# simple-loop-active2.net
KiCad netlist of a schematic drawn in EAGLE
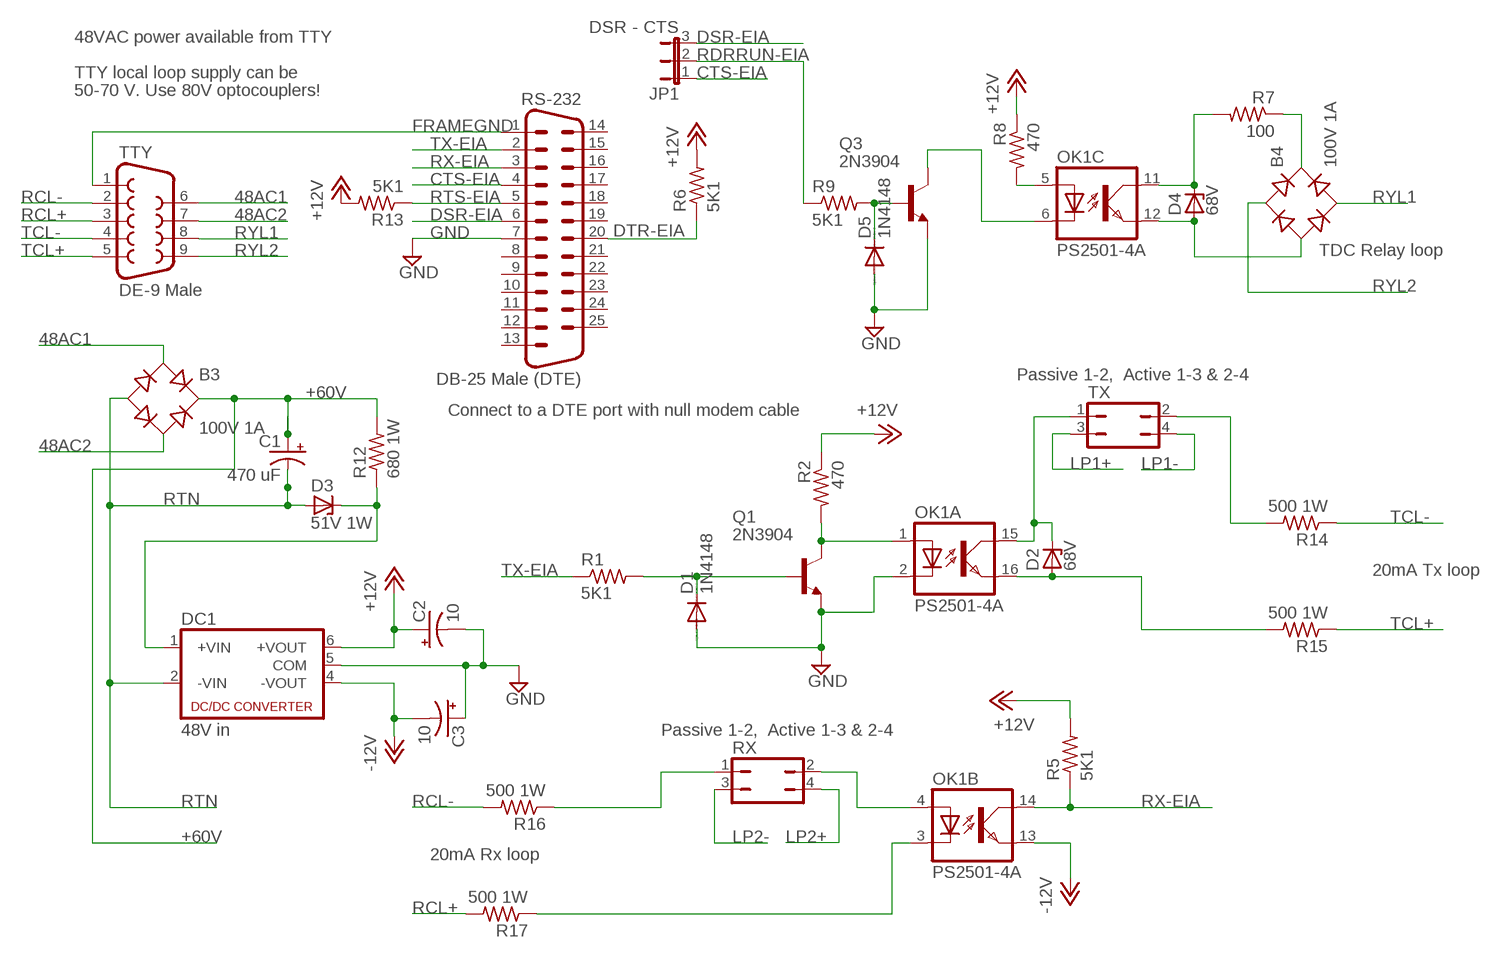
[diagram p0: schematic, sheet 1]
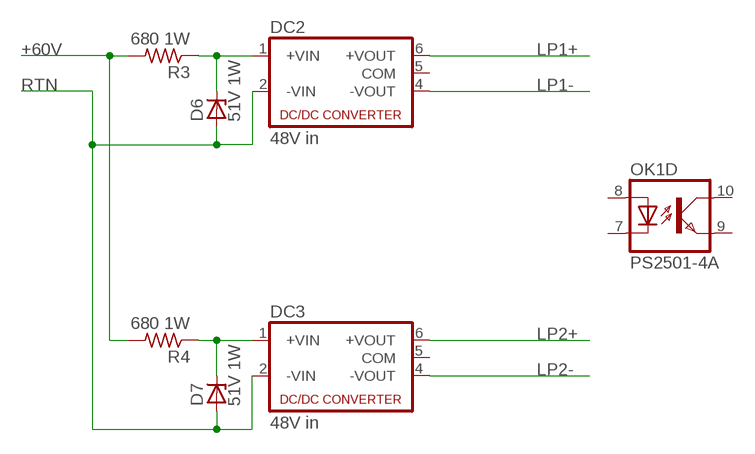
[diagram p1: schematic, sheet 2]

(export (version "E")
  (design (tool "Eeschema 10.0.6"))
  (components
    (comp (ref "B3")
      (value "100V 1A")
      (footprint "eagle-import:RB1A")
      (libsource (lib "eagle-import") (part "RB1A"))
    )
    (comp (ref "B4")
      (value "100V 1A")
      (footprint "eagle-import:RB1A")
      (libsource (lib "eagle-import") (part "RB1A"))
    )
    (comp (ref "C1")
      (value "470 uF")
      (footprint "eagle-import:E7,5-18")
      (libsource (lib "eagle-import") (part "CPOL-USE7.5-18"))
    )
    (comp (ref "C2")
      (value "10")
      (footprint "eagle-import:B45181A")
      (libsource (lib "eagle-import") (part "CPOL-USB45181A"))
    )
    (comp (ref "C3")
      (value "10")
      (footprint "eagle-import:B45181A")
      (libsource (lib "eagle-import") (part "CPOL-USB45181A"))
    )
    (comp (ref "D1")
      (value "1N4148")
      (footprint "eagle-import:DO35-10")
      (libsource (lib "eagle-import") (part "1N4148DO35-10"))
    )
    (comp (ref "D2")
      (value "68V")
      (footprint "eagle-import:DO41Z10")
      (libsource (lib "eagle-import") (part "ZENER-DIODEDO41Z10"))
    )
    (comp (ref "D3")
      (value "51V 1W")
      (footprint "eagle-import:DO41Z10")
      (libsource (lib "eagle-import") (part "ZENER-DIODEDO41Z10"))
    )
    (comp (ref "D4")
      (value "68V")
      (footprint "eagle-import:DO41Z10")
      (libsource (lib "eagle-import") (part "ZENER-DIODEDO41Z10"))
    )
    (comp (ref "D5")
      (value "1N4148")
      (footprint "eagle-import:DO35-10")
      (libsource (lib "eagle-import") (part "1N4148DO35-10"))
    )
    (comp (ref "DC1")
      (value "48V in")
      (footprint "eagle-import:NMA")
      (fields (field (name "MF") "C & D TECHNOLOGIES, INC") (field (name "MPN") "NMA0515SC"))
      (libsource (lib "eagle-import") (part "NMA"))
    )
    (comp (ref "JP1")
      (value "DSR - CTS")
      (footprint "eagle-import:JP2")
      (libsource (lib "eagle-import") (part "JP2E"))
    )
    (comp (ref "OK1")
      (value "PS2501-4A")
      (footprint "eagle-import:DIL16")
      (fields (field (name "MF") "VISHAY/TELEFUNKEN") (field (name "MPN") "ILQ1"))
      (libsource (lib "eagle-import") (part "ILQ1"))
    )
    (comp (ref "Q1")
      (value "2N3904")
      (footprint "eagle-import:TO92")
      (libsource (lib "eagle-import") (part "2N3904"))
    )
    (comp (ref "Q3")
      (value "2N3904")
      (footprint "eagle-import:TO92")
      (libsource (lib "eagle-import") (part "2N3904"))
    )
    (comp (ref "R1")
      (value "5K1")
      (footprint "eagle-import:0207_10")
      (libsource (lib "eagle-import") (part "R-US_0207/10"))
    )
    (comp (ref "R2")
      (value "470")
      (footprint "eagle-import:0207_10")
      (libsource (lib "eagle-import") (part "R-US_0207/10"))
    )
    (comp (ref "R5")
      (value "5K1")
      (footprint "eagle-import:0207_10")
      (libsource (lib "eagle-import") (part "R-US_0207/10"))
    )
    (comp (ref "R6")
      (value "5K1")
      (footprint "eagle-import:0207_10")
      (libsource (lib "eagle-import") (part "R-US_0207/10"))
    )
    (comp (ref "R7")
      (value "100")
      (footprint "eagle-import:0207_10")
      (libsource (lib "eagle-import") (part "R-US_0207/10"))
    )
    (comp (ref "R8")
      (value "470")
      (footprint "eagle-import:0207_10")
      (libsource (lib "eagle-import") (part "R-US_0207/10"))
    )
    (comp (ref "R9")
      (value "5K1")
      (footprint "eagle-import:0207_10")
      (libsource (lib "eagle-import") (part "R-US_0207/10"))
    )
    (comp (ref "R12")
      (value "680 1W")
      (footprint "eagle-import:P0817V")
      (libsource (lib "eagle-import") (part "R-US_0817/7V"))
    )
    (comp (ref "R13")
      (value "5K1")
      (footprint "eagle-import:0207_10")
      (libsource (lib "eagle-import") (part "R-US_0207/10"))
    )
    (comp (ref "R14")
      (value "500 1W")
      (footprint "eagle-import:P0817V")
      (libsource (lib "eagle-import") (part "R-US_0817/7V"))
    )
    (comp (ref "R15")
      (value "500 1W")
      (footprint "eagle-import:P0817V")
      (libsource (lib "eagle-import") (part "R-US_0817/7V"))
    )
    (comp (ref "R16")
      (value "500 1W")
      (footprint "eagle-import:P0817V")
      (libsource (lib "eagle-import") (part "R-US_0817/7V"))
    )
    (comp (ref "R17")
      (value "500 1W")
      (footprint "eagle-import:P0817V")
      (libsource (lib "eagle-import") (part "R-US_0817/7V"))
    )
    (comp (ref "RS-232")
      (value "DB-25 Male (DTE)")
      (footprint "eagle-import:M25H")
      (libsource (lib "eagle-import") (part "M25H"))
    )
    (comp (ref "RX")
      (value "JP2Q")
      (footprint "eagle-import:JP2Q")
      (libsource (lib "eagle-import") (part "JP2Q"))
    )
    (comp (ref "TTY")
      (value "DE-9 Male")
      (footprint "eagle-import:F09H")
      (libsource (lib "eagle-import") (part "F09H"))
    )
    (comp (ref "TX")
      (value "JP2Q")
      (footprint "eagle-import:JP2Q")
      (libsource (lib "eagle-import") (part "JP2Q"))
    )
    (comp (ref "D6")
      (value "51V 1W")
      (footprint "eagle-import:DO41Z10")
      (libsource (lib "eagle-import") (part "ZENER-DIODEDO41Z10"))
    )
    (comp (ref "D7")
      (value "51V 1W")
      (footprint "eagle-import:DO41Z10")
      (libsource (lib "eagle-import") (part "ZENER-DIODEDO41Z10"))
    )
    (comp (ref "DC2")
      (value "48V in")
      (footprint "eagle-import:NMA")
      (fields (field (name "MF") "C & D TECHNOLOGIES, INC") (field (name "MPN") "NMA0515SC"))
      (libsource (lib "eagle-import") (part "NMA"))
    )
    (comp (ref "DC3")
      (value "48V in")
      (footprint "eagle-import:NMA")
      (fields (field (name "MF") "C & D TECHNOLOGIES, INC") (field (name "MPN") "NMA0515SC"))
      (libsource (lib "eagle-import") (part "NMA"))
    )
    (comp (ref "R3")
      (value "680 1W")
      (footprint "eagle-import:P0817V")
      (libsource (lib "eagle-import") (part "R-US_0817/7V"))
    )
    (comp (ref "R4")
      (value "680 1W")
      (footprint "eagle-import:P0817V")
      (libsource (lib "eagle-import") (part "R-US_0817/7V"))
    )
  )
  (nets
    (net (code "1") (name "+12V") (class "Default")
      (node (ref "C2") (pin "+") (pinfunction "+_+") (pintype "passive"))
      (node (ref "DC1") (pin "6") (pinfunction "+VOUT_6") (pintype "passive"))
      (node (ref "R13") (pin "2") (pinfunction "2_2") (pintype "passive"))
      (node (ref "R2") (pin "1") (pinfunction "1_1") (pintype "passive"))
      (node (ref "R5") (pin "2") (pinfunction "2_2") (pintype "passive"))
      (node (ref "R6") (pin "2") (pinfunction "2_2") (pintype "passive"))
      (node (ref "R8") (pin "1") (pinfunction "1_1") (pintype "passive"))
    )
    (net (code "2") (name "+60V") (class "Default")
      (node (ref "B3") (pin "+") (pinfunction "+_+") (pintype "passive"))
      (node (ref "C1") (pin "+") (pinfunction "+_+") (pintype "passive"))
      (node (ref "R12") (pin "2") (pinfunction "2_2") (pintype "passive"))
      (node (ref "R3") (pin "2") (pinfunction "2_2") (pintype "passive"))
      (node (ref "R4") (pin "2") (pinfunction "2_2") (pintype "passive"))
    )
    (net (code "3") (name "-12V") (class "Default")
      (node (ref "C3") (pin "-") (pinfunction "-_-") (pintype "passive"))
      (node (ref "DC1") (pin "4") (pinfunction "-VOUT_4") (pintype "passive"))
      (node (ref "OK1") (pin "13") (pinfunction "EMIT_13") (pintype "passive"))
    )
    (net (code "4") (name "48AC1") (class "Default")
      (node (ref "B3") (pin "AC1") (pinfunction "AC1_AC1") (pintype "passive"))
      (node (ref "TTY") (pin "6") (pinfunction "6_6") (pintype "passive"))
    )
    (net (code "5") (name "48AC2") (class "Default")
      (node (ref "B3") (pin "AC2") (pinfunction "AC2_AC2") (pintype "passive"))
      (node (ref "TTY") (pin "7") (pinfunction "7_7") (pintype "passive"))
    )
    (net (code "6") (name "CTS-EIA") (class "Default")
      (node (ref "JP1") (pin "1") (pinfunction "1_1") (pintype "passive"))
      (node (ref "RS-232") (pin "4") (pinfunction "4_4") (pintype "passive"))
    )
    (net (code "7") (name "DSR-EIA") (class "Default")
      (node (ref "JP1") (pin "3") (pinfunction "3_3") (pintype "passive"))
      (node (ref "RS-232") (pin "6") (pinfunction "6_6") (pintype "passive"))
    )
    (net (code "8") (name "DTR-EIA") (class "Default")
      (node (ref "R6") (pin "1") (pinfunction "1_1") (pintype "passive"))
      (node (ref "RS-232") (pin "20") (pinfunction "20_20") (pintype "passive"))
    )
    (net (code "9") (name "FRAMEGND") (class "Default")
      (node (ref "RS-232") (pin "1") (pinfunction "1_1") (pintype "passive"))
      (node (ref "TTY") (pin "1") (pinfunction "1_1") (pintype "passive"))
    )
    (net (code "10") (name "GND") (class "Default")
      (node (ref "C2") (pin "-") (pinfunction "-_-") (pintype "passive"))
      (node (ref "C3") (pin "+") (pinfunction "+_+") (pintype "passive"))
      (node (ref "D1") (pin "A") (pinfunction "A_A") (pintype "passive"))
      (node (ref "D5") (pin "A") (pinfunction "A_A") (pintype "passive"))
      (node (ref "DC1") (pin "5") (pinfunction "COM_5") (pintype "passive"))
      (node (ref "OK1") (pin "2") (pinfunction "C_2") (pintype "passive"))
      (node (ref "Q1") (pin "3") (pinfunction "E_3") (pintype "passive"))
      (node (ref "Q3") (pin "3") (pinfunction "E_3") (pintype "passive"))
      (node (ref "RS-232") (pin "7") (pinfunction "7_7") (pintype "passive"))
    )
    (net (code "11") (name "LP1+") (class "Default")
      (node (ref "DC2") (pin "6") (pinfunction "+VOUT_6") (pintype "passive"))
      (node (ref "TX") (pin "3") (pinfunction "3_3") (pintype "passive"))
    )
    (net (code "12") (name "LP1-") (class "Default")
      (node (ref "DC2") (pin "4") (pinfunction "-VOUT_4") (pintype "passive"))
      (node (ref "TX") (pin "4") (pinfunction "4_4") (pintype "passive"))
    )
    (net (code "13") (name "LP2+") (class "Default")
      (node (ref "DC3") (pin "6") (pinfunction "+VOUT_6") (pintype "passive"))
      (node (ref "RX") (pin "4") (pinfunction "4_4") (pintype "passive"))
    )
    (net (code "14") (name "LP2-") (class "Default")
      (node (ref "DC3") (pin "4") (pinfunction "-VOUT_4") (pintype "passive"))
      (node (ref "RX") (pin "3") (pinfunction "3_3") (pintype "passive"))
    )
    (net (code "15") (name "Net-(B4-Pad+)") (class "Default")
      (node (ref "B4") (pin "+") (pinfunction "+_+") (pintype "passive"))
      (node (ref "R7") (pin "1") (pinfunction "1_1") (pintype "passive"))
    )
    (net (code "16") (name "Net-(DC1-+VIN)") (class "Default")
      (node (ref "D3") (pin "C") (pinfunction "C_C") (pintype "passive"))
      (node (ref "DC1") (pin "1") (pinfunction "+VIN_1") (pintype "passive"))
      (node (ref "R12") (pin "1") (pinfunction "1_1") (pintype "passive"))
    )
    (net (code "17") (name "Net-(DC2-+VIN)") (class "Default")
      (node (ref "D6") (pin "C") (pinfunction "C_C") (pintype "passive"))
      (node (ref "DC2") (pin "1") (pinfunction "+VIN_1") (pintype "passive"))
      (node (ref "R3") (pin "1") (pinfunction "1_1") (pintype "passive"))
    )
    (net (code "18") (name "Net-(DC3-+VIN)") (class "Default")
      (node (ref "D7") (pin "C") (pinfunction "C_C") (pintype "passive"))
      (node (ref "DC3") (pin "1") (pinfunction "+VIN_1") (pintype "passive"))
      (node (ref "R4") (pin "1") (pinfunction "1_1") (pintype "passive"))
    )
    (net (code "19") (name "Net-(OK1A-A)") (class "Default")
      (node (ref "OK1") (pin "1") (pinfunction "A_1") (pintype "passive"))
      (node (ref "Q1") (pin "1") (pinfunction "C_1") (pintype "passive"))
      (node (ref "R2") (pin "2") (pinfunction "2_2") (pintype "passive"))
    )
    (net (code "20") (name "Net-(OK1A-COL)") (class "Default")
      (node (ref "D2") (pin "C") (pinfunction "C_C") (pintype "passive"))
      (node (ref "OK1") (pin "15") (pinfunction "COL_15") (pintype "passive"))
      (node (ref "TX") (pin "1") (pinfunction "1_1") (pintype "passive"))
    )
    (net (code "21") (name "Net-(OK1A-EMIT)") (class "Default")
      (node (ref "D2") (pin "A") (pinfunction "A_A") (pintype "passive"))
      (node (ref "OK1") (pin "16") (pinfunction "EMIT_16") (pintype "passive"))
      (node (ref "R15") (pin "2") (pinfunction "2_2") (pintype "passive"))
    )
    (net (code "22") (name "Net-(OK1B-A)") (class "Default")
      (node (ref "OK1") (pin "4") (pinfunction "A_4") (pintype "passive"))
      (node (ref "RX") (pin "2") (pinfunction "2_2") (pintype "passive"))
    )
    (net (code "23") (name "Net-(OK1B-C)") (class "Default")
      (node (ref "OK1") (pin "3") (pinfunction "C_3") (pintype "passive"))
      (node (ref "R17") (pin "1") (pinfunction "1_1") (pintype "passive"))
    )
    (net (code "24") (name "Net-(OK1C-A)") (class "Default")
      (node (ref "OK1") (pin "5") (pinfunction "A_5") (pintype "passive"))
      (node (ref "R8") (pin "2") (pinfunction "2_2") (pintype "passive"))
    )
    (net (code "25") (name "Net-(OK1C-C)") (class "Default")
      (node (ref "OK1") (pin "6") (pinfunction "C_6") (pintype "passive"))
      (node (ref "Q3") (pin "1") (pinfunction "C_1") (pintype "passive"))
    )
    (net (code "26") (name "Net-(OK1C-COL)") (class "Default")
      (node (ref "D4") (pin "C") (pinfunction "C_C") (pintype "passive"))
      (node (ref "OK1") (pin "11") (pinfunction "COL_11") (pintype "passive"))
      (node (ref "R7") (pin "2") (pinfunction "2_2") (pintype "passive"))
    )
    (net (code "27") (name "Net-(OK1C-EMIT)") (class "Default")
      (node (ref "B4") (pin "-") (pinfunction "-_-") (pintype "passive"))
      (node (ref "D4") (pin "A") (pinfunction "A_A") (pintype "passive"))
      (node (ref "OK1") (pin "12") (pinfunction "EMIT_12") (pintype "passive"))
    )
    (net (code "28") (name "Net-(Q1-B)") (class "Default")
      (node (ref "D1") (pin "C") (pinfunction "C_C") (pintype "passive"))
      (node (ref "Q1") (pin "2") (pinfunction "B_2") (pintype "passive"))
      (node (ref "R1") (pin "2") (pinfunction "2_2") (pintype "passive"))
    )
    (net (code "29") (name "Net-(Q3-B)") (class "Default")
      (node (ref "D5") (pin "C") (pinfunction "C_C") (pintype "passive"))
      (node (ref "Q3") (pin "2") (pinfunction "B_2") (pintype "passive"))
      (node (ref "R9") (pin "2") (pinfunction "2_2") (pintype "passive"))
    )
    (net (code "30") (name "Net-(R14-Pad2)") (class "Default")
      (node (ref "R14") (pin "2") (pinfunction "2_2") (pintype "passive"))
      (node (ref "TX") (pin "2") (pinfunction "2_2") (pintype "passive"))
    )
    (net (code "31") (name "Net-(R16-Pad1)") (class "Default")
      (node (ref "R16") (pin "1") (pinfunction "1_1") (pintype "passive"))
      (node (ref "RX") (pin "1") (pinfunction "1_1") (pintype "passive"))
    )
    (net (code "32") (name "RCL+") (class "Default")
      (node (ref "R17") (pin "2") (pinfunction "2_2") (pintype "passive"))
      (node (ref "TTY") (pin "3") (pinfunction "3_3") (pintype "passive"))
    )
    (net (code "33") (name "RCL-") (class "Default")
      (node (ref "R16") (pin "2") (pinfunction "2_2") (pintype "passive"))
      (node (ref "TTY") (pin "2") (pinfunction "2_2") (pintype "passive"))
    )
    (net (code "34") (name "RDRRUN-EIA") (class "Default")
      (node (ref "JP1") (pin "2") (pinfunction "2_2") (pintype "passive"))
      (node (ref "R9") (pin "1") (pinfunction "1_1") (pintype "passive"))
    )
    (net (code "35") (name "RTN") (class "Default")
      (node (ref "B3") (pin "-") (pinfunction "-_-") (pintype "passive"))
      (node (ref "C1") (pin "-") (pinfunction "-_-") (pintype "passive"))
      (node (ref "D3") (pin "A") (pinfunction "A_A") (pintype "passive"))
      (node (ref "D6") (pin "A") (pinfunction "A_A") (pintype "passive"))
      (node (ref "D7") (pin "A") (pinfunction "A_A") (pintype "passive"))
      (node (ref "DC1") (pin "2") (pinfunction "-VIN_2") (pintype "passive"))
      (node (ref "DC2") (pin "2") (pinfunction "-VIN_2") (pintype "passive"))
      (node (ref "DC3") (pin "2") (pinfunction "-VIN_2") (pintype "passive"))
    )
    (net (code "36") (name "RTS-EIA") (class "Default")
      (node (ref "R13") (pin "1") (pinfunction "1_1") (pintype "passive"))
      (node (ref "RS-232") (pin "5") (pinfunction "5_5") (pintype "passive"))
    )
    (net (code "37") (name "RX-EIA") (class "Default")
      (node (ref "OK1") (pin "14") (pinfunction "COL_14") (pintype "passive"))
      (node (ref "R5") (pin "1") (pinfunction "1_1") (pintype "passive"))
      (node (ref "RS-232") (pin "3") (pinfunction "3_3") (pintype "passive"))
    )
    (net (code "38") (name "RYL1") (class "Default")
      (node (ref "B4") (pin "AC2") (pinfunction "AC2_AC2") (pintype "passive"))
      (node (ref "TTY") (pin "8") (pinfunction "8_8") (pintype "passive"))
    )
    (net (code "39") (name "RYL2") (class "Default")
      (node (ref "B4") (pin "AC1") (pinfunction "AC1_AC1") (pintype "passive"))
      (node (ref "TTY") (pin "9") (pinfunction "9_9") (pintype "passive"))
    )
    (net (code "40") (name "TCL+") (class "Default")
      (node (ref "R15") (pin "1") (pinfunction "1_1") (pintype "passive"))
      (node (ref "TTY") (pin "5") (pinfunction "5_5") (pintype "passive"))
    )
    (net (code "41") (name "TCL-") (class "Default")
      (node (ref "R14") (pin "1") (pinfunction "1_1") (pintype "passive"))
      (node (ref "TTY") (pin "4") (pinfunction "4_4") (pintype "passive"))
    )
    (net (code "42") (name "TX-EIA") (class "Default")
      (node (ref "R1") (pin "1") (pinfunction "1_1") (pintype "passive"))
      (node (ref "RS-232") (pin "2") (pinfunction "2_2") (pintype "passive"))
    )
    (net (code "43") (name "unconnected-(DC2-COM-Pad5)") (class "Default")
      (node (ref "DC2") (pin "5") (pinfunction "COM_5") (pintype "passive"))
    )
    (net (code "44") (name "unconnected-(DC3-COM-Pad5)") (class "Default")
      (node (ref "DC3") (pin "5") (pinfunction "COM_5") (pintype "passive"))
    )
    (net (code "45") (name "unconnected-(OK1D-A-Pad8)") (class "Default")
      (node (ref "OK1") (pin "8") (pinfunction "A_8") (pintype "passive"))
    )
    (net (code "46") (name "unconnected-(OK1D-C-Pad7)") (class "Default")
      (node (ref "OK1") (pin "7") (pinfunction "C_7") (pintype "passive"))
    )
    (net (code "47") (name "unconnected-(OK1D-COL-Pad10)") (class "Default")
      (node (ref "OK1") (pin "10") (pinfunction "COL_10") (pintype "passive"))
    )
    (net (code "48") (name "unconnected-(OK1D-EMIT-Pad9)") (class "Default")
      (node (ref "OK1") (pin "9") (pinfunction "EMIT_9") (pintype "passive"))
    )
    (net (code "49") (name "unconnected-(RS-232-Pad8)") (class "Default")
      (node (ref "RS-232") (pin "8") (pinfunction "8_8") (pintype "passive"))
    )
    (net (code "50") (name "unconnected-(RS-232-Pad9)") (class "Default")
      (node (ref "RS-232") (pin "9") (pinfunction "9_9") (pintype "passive"))
    )
    (net (code "51") (name "unconnected-(RS-232-Pad10)") (class "Default")
      (node (ref "RS-232") (pin "10") (pinfunction "10_10") (pintype "passive"))
    )
    (net (code "52") (name "unconnected-(RS-232-Pad11)") (class "Default")
      (node (ref "RS-232") (pin "11") (pinfunction "11_11") (pintype "passive"))
    )
    (net (code "53") (name "unconnected-(RS-232-Pad12)") (class "Default")
      (node (ref "RS-232") (pin "12") (pinfunction "12_12") (pintype "passive"))
    )
    (net (code "54") (name "unconnected-(RS-232-Pad13)") (class "Default")
      (node (ref "RS-232") (pin "13") (pinfunction "13_13") (pintype "passive"))
    )
    (net (code "55") (name "unconnected-(RS-232-Pad14)") (class "Default")
      (node (ref "RS-232") (pin "14") (pinfunction "14_14") (pintype "passive"))
    )
    (net (code "56") (name "unconnected-(RS-232-Pad15)") (class "Default")
      (node (ref "RS-232") (pin "15") (pinfunction "15_15") (pintype "passive"))
    )
    (net (code "57") (name "unconnected-(RS-232-Pad16)") (class "Default")
      (node (ref "RS-232") (pin "16") (pinfunction "16_16") (pintype "passive"))
    )
    (net (code "58") (name "unconnected-(RS-232-Pad17)") (class "Default")
      (node (ref "RS-232") (pin "17") (pinfunction "17_17") (pintype "passive"))
    )
    (net (code "59") (name "unconnected-(RS-232-Pad18)") (class "Default")
      (node (ref "RS-232") (pin "18") (pinfunction "18_18") (pintype "passive"))
    )
    (net (code "60") (name "unconnected-(RS-232-Pad19)") (class "Default")
      (node (ref "RS-232") (pin "19") (pinfunction "19_19") (pintype "passive"))
    )
    (net (code "61") (name "unconnected-(RS-232-Pad21)") (class "Default")
      (node (ref "RS-232") (pin "21") (pinfunction "21_21") (pintype "passive"))
    )
    (net (code "62") (name "unconnected-(RS-232-Pad22)") (class "Default")
      (node (ref "RS-232") (pin "22") (pinfunction "22_22") (pintype "passive"))
    )
    (net (code "63") (name "unconnected-(RS-232-Pad23)") (class "Default")
      (node (ref "RS-232") (pin "23") (pinfunction "23_23") (pintype "passive"))
    )
    (net (code "64") (name "unconnected-(RS-232-Pad24)") (class "Default")
      (node (ref "RS-232") (pin "24") (pinfunction "24_24") (pintype "passive"))
    )
    (net (code "65") (name "unconnected-(RS-232-Pad25)") (class "Default")
      (node (ref "RS-232") (pin "25") (pinfunction "25_25") (pintype "passive"))
    )
  )
)
